# pdivider.net
KiCad netlist of a schematic drawn in EAGLE
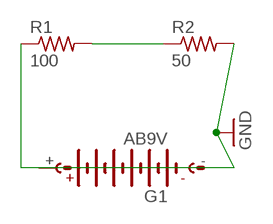
[diagram p0: schematic, sheet 1]

(export (version "E")
  (design (tool "Eeschema 10.0.6"))
  (components
    (comp (ref "G1")
      (value "AB9V")
      (footprint "eagle-import:AB9V")
      (libsource (lib "eagle-import") (part "AB9V"))
    )
    (comp (ref "R1")
      (value "100")
      (footprint "eagle-import:R0603")
      (libsource (lib "eagle-import") (part "R-US_R0603"))
    )
    (comp (ref "R2")
      (value "50")
      (footprint "eagle-import:R0603")
      (libsource (lib "eagle-import") (part "R-US_R0603"))
    )
  )
  (nets
    (net (code "1") (name "GND") (class "Default")
      (node (ref "G1") (pin "+") (pinfunction "+_+") (pintype "passive"))
      (node (ref "R2") (pin "2") (pinfunction "2_2") (pintype "passive"))
    )
    (net (code "2") (name "Net-(G1-Pad-)") (class "Default")
      (node (ref "G1") (pin "-") (pinfunction "-_-") (pintype "passive"))
      (node (ref "R1") (pin "1") (pinfunction "1_1") (pintype "passive"))
    )
    (net (code "3") (name "Net-(R1-Pad2)") (class "Default")
      (node (ref "R1") (pin "2") (pinfunction "2_2") (pintype "passive"))
      (node (ref "R2") (pin "1") (pinfunction "1_1") (pintype "passive"))
    )
  )
)
